# Sheet1.net
KiCad netlist of a schematic drawn in Altium Designer
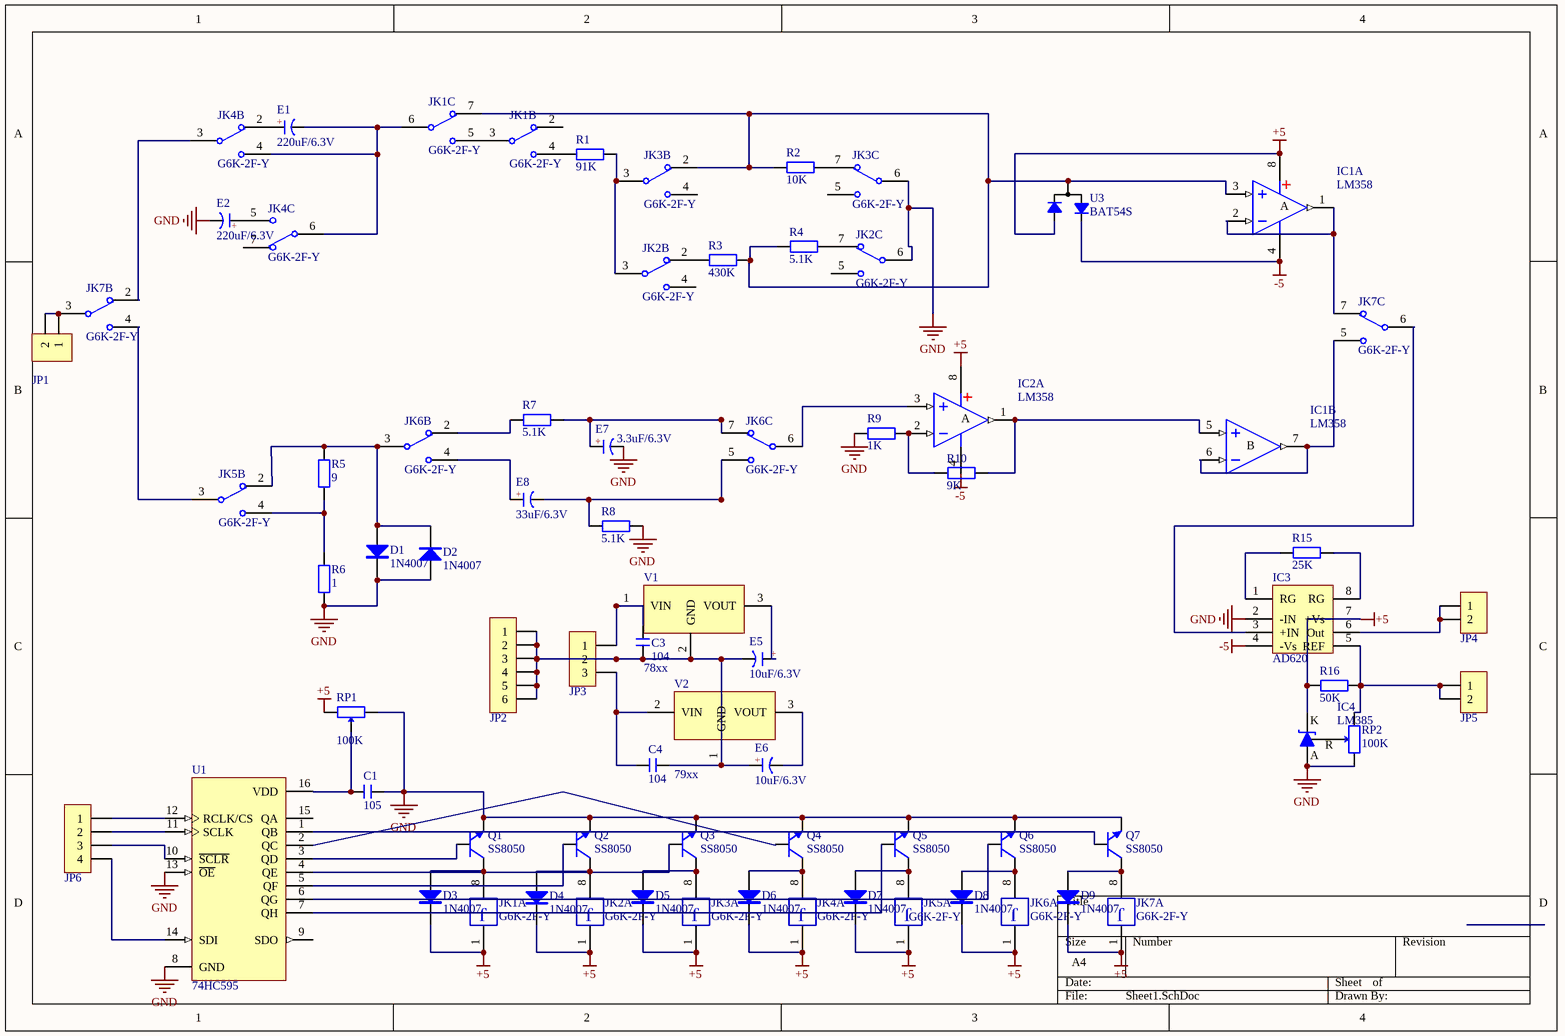
[diagram p0: Sheet1.SchDoc]

(export (version "E")
  (design (tool "Eeschema 10.0.6"))
  (components
    (comp (ref "C1")
      (value "105")
      (footprint "C 0805_L")
      (description "无极性贴片电容")
      (fields (field (name "版权归属") "源创客"))
      (libsource (lib "3.1   - 电阻-电容-电感") (part "C"))
    )
    (comp (ref "C3")
      (value "104")
      (footprint "C 0805_L")
      (description "无极性贴片电容")
      (fields (field (name "版权归属") "源创客"))
      (libsource (lib "3.1   - 电阻-电容-电感") (part "C"))
    )
    (comp (ref "C4")
      (value "104")
      (footprint "C 0805_L")
      (description "无极性贴片电容")
      (fields (field (name "版权归属") "源创客"))
      (libsource (lib "3.1   - 电阻-电容-电感") (part "C"))
    )
    (comp (ref "D1")
      (value "1N4007")
      (footprint "DO-41")
      (description "整流二极管")
      (fields (field (name "版权归属") "源创客"))
      (libsource (lib "8.1   - 二极管-整流桥") (part "1N4007"))
    )
    (comp (ref "D2")
      (value "1N4007")
      (footprint "DO-41")
      (description "整流二极管")
      (fields (field (name "版权归属") "源创客"))
      (libsource (lib "8.1   - 二极管-整流桥") (part "1N4007"))
    )
    (comp (ref "D3")
      (value "1N4007")
      (footprint "DO-41")
      (description "整流二极管")
      (fields (field (name "版权归属") "源创客"))
      (libsource (lib "8.1   - 二极管-整流桥") (part "1N4007"))
    )
    (comp (ref "D4")
      (value "1N4007")
      (footprint "DO-41")
      (description "整流二极管")
      (fields (field (name "版权归属") "源创客"))
      (libsource (lib "8.1   - 二极管-整流桥") (part "1N4007"))
    )
    (comp (ref "D5")
      (value "1N4007")
      (footprint "DO-41")
      (description "整流二极管")
      (fields (field (name "版权归属") "源创客"))
      (libsource (lib "8.1   - 二极管-整流桥") (part "1N4007"))
    )
    (comp (ref "D6")
      (value "1N4007")
      (footprint "DO-41")
      (description "整流二极管")
      (fields (field (name "版权归属") "源创客"))
      (libsource (lib "8.1   - 二极管-整流桥") (part "1N4007"))
    )
    (comp (ref "D7")
      (value "1N4007")
      (footprint "DO-41")
      (description "整流二极管")
      (fields (field (name "版权归属") "源创客"))
      (libsource (lib "8.1   - 二极管-整流桥") (part "1N4007"))
    )
    (comp (ref "D8")
      (value "1N4007")
      (footprint "DO-41")
      (description "整流二极管")
      (fields (field (name "版权归属") "源创客"))
      (libsource (lib "8.1   - 二极管-整流桥") (part "1N4007"))
    )
    (comp (ref "D9")
      (value "1N4007")
      (footprint "DO-41")
      (description "整流二极管")
      (fields (field (name "版权归属") "源创客"))
      (libsource (lib "8.1   - 二极管-整流桥") (part "1N4007"))
    )
    (comp (ref "E1")
      (value "220uF/6.3V")
      (footprint "CS 2.0*5*8 - C")
      (description "直插固态电容")
      (fields (field (name "版权归属") "源创客"))
      (libsource (lib "3.1   - 电阻-电容-电感") (part "C-CS"))
    )
    (comp (ref "E2")
      (value "220uF/6.3V")
      (footprint "CS 2.0*5*8 - C")
      (description "直插固态电容")
      (fields (field (name "版权归属") "源创客"))
      (libsource (lib "3.1   - 电阻-电容-电感") (part "C-CS"))
    )
    (comp (ref "E5")
      (value "10uF/6.3V")
      (footprint "CS 2.0*5*8 - C")
      (description "直插固态电容")
      (fields (field (name "版权归属") "源创客"))
      (libsource (lib "") (part "C-CS_1"))
    )
    (comp (ref "E6")
      (value "10uF/6.3V")
      (footprint "CS 2.0*5*8 - C")
      (description "直插固态电容")
      (fields (field (name "版权归属") "源创客"))
      (libsource (lib "3.1   - 电阻-电容-电感") (part "C-CS"))
    )
    (comp (ref "E7")
      (value "3.3uF/6.3V")
      (footprint "CS 2.0*5*8 - C")
      (description "直插固态电容")
      (fields (field (name "版权归属") "源创客"))
      (libsource (lib "3.1   - 电阻-电容-电感") (part "C-CS"))
    )
    (comp (ref "E8")
      (value "33uF/6.3V")
      (footprint "CS 2.0*5*8 - C")
      (description "直插固态电容")
      (fields (field (name "版权归属") "源创客"))
      (libsource (lib "3.1   - 电阻-电容-电感") (part "C-CS"))
    )
    (comp (ref "IC1")
      (value "LM358")
      (footprint "SOP8_N")
      (description "双路运放")
      (fields (field (name "版权归属") "源创客"))
      (libsource (lib "1.1   - IC芯片") (part "LM358"))
    )
    (comp (ref "IC2")
      (value "LM358")
      (footprint "SOP8_N")
      (description "双路运放")
      (fields (field (name "版权归属") "源创客"))
      (libsource (lib "1.1   - IC芯片") (part "LM358"))
    )
    (comp (ref "IC3")
      (value "AD620")
      (footprint "SOP8_N")
      (description "仪表放大器")
      (libsource (lib "1.1   - IC芯片") (part "AD620"))
    )
    (comp (ref "IC4")
      (value "LM385")
      (footprint "TO92A")
      (description "可调基准稳压芯片")
      (fields (field (name "版权归属") "源创客"))
      (libsource (lib "1.3   - 电源类芯片") (part "TL431-ID"))
    )
    (comp (ref "JK1")
      (value "G6K-2F-Y")
      (footprint "G6K-2F-Y")
      (description "两组转换-信号型")
      (libsource (lib "") (part "G6K-2F-Y_2"))
    )
    (comp (ref "JK2")
      (value "G6K-2F-Y")
      (footprint "G6K-2F-Y")
      (description "两组转换-信号型")
      (libsource (lib "0.9 - 继电器-变压器") (part "G6K-2F-Y"))
    )
    (comp (ref "JK3")
      (value "G6K-2F-Y")
      (footprint "G6K-2F-Y")
      (description "两组转换-信号型")
      (libsource (lib "0.9 - 继电器-变压器") (part "G6K-2F-Y"))
    )
    (comp (ref "JK4")
      (value "G6K-2F-Y")
      (footprint "G6K-2F-Y")
      (description "两组转换-信号型")
      (libsource (lib "") (part "G6K-2F-Y_1"))
    )
    (comp (ref "JK5")
      (value "G6K-2F-Y")
      (footprint "G6K-2F-Y")
      (description "两组转换-信号型")
      (libsource (lib "0.9 - 继电器-变压器") (part "G6K-2F-Y"))
    )
    (comp (ref "JK6")
      (value "G6K-2F-Y")
      (footprint "G6K-2F-Y")
      (description "两组转换-信号型")
      (libsource (lib "0.9 - 继电器-变压器") (part "G6K-2F-Y"))
    )
    (comp (ref "JK7")
      (value "G6K-2F-Y")
      (footprint "G6K-2F-Y")
      (description "两组转换-信号型")
      (libsource (lib "0.9 - 继电器-变压器") (part "G6K-2F-Y"))
    )
    (comp (ref "JP1")
      (value "HDR-1X2")
      (footprint "HDR2.54-LI-2P")
      (description "2P接插件")
      (fields (field (name "版权归属") "源创客"))
      (libsource (lib "") (part "Header 2_1"))
    )
    (comp (ref "JP2")
      (value "HDR-1X6")
      (footprint "HDR2.54-LI-6P")
      (description "6P接插件")
      (fields (field (name "版权归属") "源创客"))
      (libsource (lib "4.5   - 接插件-脚距2.54") (part "Header 6"))
    )
    (comp (ref "JP3")
      (value "HDR-1X3")
      (footprint "VH3.96-LI-3P")
      (description "3P接插件")
      (fields (field (name "版权归属") "源创客"))
      (libsource (lib "4.8   - 接插件-脚距3.96") (part "Header 3"))
    )
    (comp (ref "JP4")
      (value "HDR-1X2")
      (footprint "HDR2.54-LI-2P")
      (description "2P接插件")
      (fields (field (name "版权归属") "源创客"))
      (libsource (lib "4.5   - 接插件-脚距2.54") (part "Header 2"))
    )
    (comp (ref "JP5")
      (value "HDR-1X2")
      (footprint "HDR2.54-LI-2P")
      (description "2P接插件")
      (fields (field (name "版权归属") "源创客"))
      (libsource (lib "4.5   - 接插件-脚距2.54") (part "Header 2"))
    )
    (comp (ref "JP6")
      (value "HDR-1X4")
      (footprint "HDR2.54-LI-4P")
      (description "4P接插件")
      (fields (field (name "版权归属") "源创客"))
      (libsource (lib "4.5   - 接插件-脚距2.54") (part "Header 4"))
    )
    (comp (ref "Q1")
      (value "SS8050")
      (footprint "SOT23-3N")
      (description "高频放大-NPN型")
      (fields (field (name "版权归属") "源创客"))
      (libsource (lib "6.2   - 三极管") (part "8050-SMD"))
    )
    (comp (ref "Q2")
      (value "SS8050")
      (footprint "SOT23-3N")
      (description "高频放大-NPN型")
      (fields (field (name "版权归属") "源创客"))
      (libsource (lib "6.2   - 三极管") (part "8050-SMD"))
    )
    (comp (ref "Q3")
      (value "SS8050")
      (footprint "SOT23-3N")
      (description "高频放大-NPN型")
      (fields (field (name "版权归属") "源创客"))
      (libsource (lib "6.2   - 三极管") (part "8050-SMD"))
    )
    (comp (ref "Q4")
      (value "SS8050")
      (footprint "SOT23-3N")
      (description "高频放大-NPN型")
      (fields (field (name "版权归属") "源创客"))
      (libsource (lib "6.2   - 三极管") (part "8050-SMD"))
    )
    (comp (ref "Q5")
      (value "SS8050")
      (footprint "SOT23-3N")
      (description "高频放大-NPN型")
      (fields (field (name "版权归属") "源创客"))
      (libsource (lib "6.2   - 三极管") (part "8050-SMD"))
    )
    (comp (ref "Q6")
      (value "SS8050")
      (footprint "SOT23-3N")
      (description "高频放大-NPN型")
      (fields (field (name "版权归属") "源创客"))
      (libsource (lib "6.2   - 三极管") (part "8050-SMD"))
    )
    (comp (ref "Q7")
      (value "SS8050")
      (footprint "SOT23-3N")
      (description "高频放大-NPN型")
      (fields (field (name "版权归属") "源创客"))
      (libsource (lib "6.2   - 三极管") (part "8050-SMD"))
    )
    (comp (ref "R1")
      (value "91K")
      (footprint "R 0805_L")
      (description "贴片电阻")
      (fields (field (name "版权归属") "源创客"))
      (libsource (lib "3.1   - 电阻-电容-电感") (part "R"))
    )
    (comp (ref "R2")
      (value "10K")
      (footprint "R 0805_L")
      (description "贴片电阻")
      (fields (field (name "版权归属") "源创客"))
      (libsource (lib "3.1   - 电阻-电容-电感") (part "R"))
    )
    (comp (ref "R3")
      (value "430K")
      (footprint "R 0805_L")
      (description "贴片电阻")
      (fields (field (name "版权归属") "源创客"))
      (libsource (lib "3.1   - 电阻-电容-电感") (part "R"))
    )
    (comp (ref "R4")
      (value "5.1K")
      (footprint "R 0805_L")
      (description "贴片电阻")
      (fields (field (name "版权归属") "源创客"))
      (libsource (lib "3.1   - 电阻-电容-电感") (part "R"))
    )
    (comp (ref "R5")
      (value "9")
      (footprint "R 0805_L")
      (description "贴片电阻")
      (fields (field (name "版权归属") "源创客"))
      (libsource (lib "3.1   - 电阻-电容-电感") (part "R"))
    )
    (comp (ref "R6")
      (value "1")
      (footprint "R 0805_L")
      (description "贴片电阻")
      (fields (field (name "版权归属") "源创客"))
      (libsource (lib "3.1   - 电阻-电容-电感") (part "R"))
    )
    (comp (ref "R7")
      (value "5.1K")
      (footprint "R 0805_L")
      (description "贴片电阻")
      (fields (field (name "版权归属") "源创客"))
      (libsource (lib "3.1   - 电阻-电容-电感") (part "R"))
    )
    (comp (ref "R8")
      (value "5.1K")
      (footprint "R 0805_L")
      (description "贴片电阻")
      (fields (field (name "版权归属") "源创客"))
      (libsource (lib "3.1   - 电阻-电容-电感") (part "R"))
    )
    (comp (ref "R9")
      (value "1K")
      (footprint "R 0805_L")
      (description "贴片电阻")
      (fields (field (name "版权归属") "源创客"))
      (libsource (lib "3.1   - 电阻-电容-电感") (part "R"))
    )
    (comp (ref "R10")
      (value "9K")
      (footprint "R 0805_L")
      (description "贴片电阻")
      (fields (field (name "版权归属") "源创客"))
      (libsource (lib "3.1   - 电阻-电容-电感") (part "R"))
    )
    (comp (ref "R15")
      (value "25K")
      (footprint "R 0805_L")
      (description "贴片电阻")
      (fields (field (name "版权归属") "源创客"))
      (libsource (lib "3.1   - 电阻-电容-电感") (part "R"))
    )
    (comp (ref "R16")
      (value "50K")
      (footprint "R 0805_L")
      (description "贴片电阻")
      (fields (field (name "版权归属") "源创客"))
      (libsource (lib "3.1   - 电阻-电容-电感") (part "R"))
    )
    (comp (ref "RP1")
      (value "100K")
      (footprint "3296W")
      (description "插件单联电位器")
      (fields (field (name "版权归属") "源创客"))
      (libsource (lib "3.1   - 电阻-电容-电感") (part "RP-ID"))
    )
    (comp (ref "RP2")
      (value "100K")
      (footprint "3296W")
      (description "插件单联电位器")
      (fields (field (name "版权归属") "源创客"))
      (libsource (lib "3.1   - 电阻-电容-电感") (part "RP-ID"))
    )
    (comp (ref "U1")
      (value "74HC595")
      (footprint "SOIC-16")
      (description "移位寄存器")
      (fields (field (name "PUBLISHER") "Altium Limited"))
      (libsource (lib "CommonUsed") (part "74HC595"))
    )
    (comp (ref "U3") (value "BAT54S") (footprint "SOT-23-3") (libsource (lib "CommonUsed") (part "BAT54S")))
    (comp (ref "V1")
      (value "78xx")
      (footprint "TO220A")
      (description "线性稳压芯片")
      (fields (field (name "版权归属") "源创客"))
      (libsource (lib "1.3   - 电源类芯片") (part "78xx"))
    )
    (comp (ref "V2")
      (value "79xx")
      (footprint "TO220A")
      (description "线性稳压芯片")
      (fields (field (name "版权归属") "源创客"))
      (libsource (lib "1.3   - 电源类芯片") (part "79xx"))
    )
  )
  (nets
    (net (code "1") (name "+5") (class "Default")
      (node (ref "D3") (pin "2") (pinfunction "K_2") (pintype "passive"))
      (node (ref "D4") (pin "2") (pinfunction "K_2") (pintype "passive"))
      (node (ref "D5") (pin "2") (pinfunction "K_2") (pintype "passive"))
      (node (ref "D6") (pin "2") (pinfunction "K_2") (pintype "passive"))
      (node (ref "D7") (pin "2") (pinfunction "K_2") (pintype "passive"))
      (node (ref "D8") (pin "2") (pinfunction "K_2") (pintype "passive"))
      (node (ref "D9") (pin "2") (pinfunction "K_2") (pintype "passive"))
      (node (ref "IC1") (pin "8") (pinfunction "V+_8") (pintype "power_in"))
      (node (ref "IC2") (pin "8") (pinfunction "V+_8") (pintype "power_in"))
      (node (ref "JK1") (pin "1") (pinfunction "1_1") (pintype "passive"))
      (node (ref "JK2") (pin "1") (pinfunction "1_1") (pintype "passive"))
      (node (ref "JK3") (pin "1") (pinfunction "1_1") (pintype "passive"))
      (node (ref "JK4") (pin "1") (pinfunction "1_1") (pintype "passive"))
      (node (ref "JK5") (pin "1") (pinfunction "1_1") (pintype "passive"))
      (node (ref "JK6") (pin "1") (pinfunction "1_1") (pintype "passive"))
      (node (ref "JK7") (pin "1") (pinfunction "1_1") (pintype "passive"))
      (node (ref "RP1") (pin "3") (pinfunction "3_3") (pintype "passive"))
      (node (ref "U3") (pin "1") (pinfunction "1_1") (pintype "passive"))
    )
    (net (code "2") (name "-5") (class "Default")
      (node (ref "IC1") (pin "4") (pinfunction "V-_4") (pintype "power_in"))
      (node (ref "IC2") (pin "4") (pinfunction "V-_4") (pintype "power_in"))
      (node (ref "IC3") (pin "4") (pinfunction "-Vs_4") (pintype "passive"))
      (node (ref "U3") (pin "3") (pinfunction "3_3") (pintype "passive"))
    )
    (net (code "3") (name "GND") (class "Default")
      (node (ref "C1") (pin "2") (pinfunction "2_2") (pintype "passive"))
      (node (ref "D1") (pin "2") (pinfunction "K_2") (pintype "passive"))
      (node (ref "D2") (pin "1") (pinfunction "A_1") (pintype "passive"))
      (node (ref "E2") (pin "2") (pinfunction "K_2") (pintype "passive"))
      (node (ref "E7") (pin "2") (pinfunction "K_2") (pintype "passive"))
      (node (ref "IC3") (pin "2") (pinfunction "-IN_2") (pintype "passive"))
      (node (ref "IC4") (pin "2") (pinfunction "A_2") (pintype "passive"))
      (node (ref "JK2") (pin "6") (pinfunction "6_6") (pintype "passive"))
      (node (ref "JK3") (pin "6") (pinfunction "6_6") (pintype "passive"))
      (node (ref "Q1") (pin "2") (pinfunction "E_2") (pintype "passive"))
      (node (ref "Q2") (pin "2") (pinfunction "E_2") (pintype "passive"))
      (node (ref "Q3") (pin "2") (pinfunction "E_2") (pintype "passive"))
      (node (ref "Q4") (pin "2") (pinfunction "E_2") (pintype "passive"))
      (node (ref "Q5") (pin "2") (pinfunction "E_2") (pintype "passive"))
      (node (ref "Q6") (pin "2") (pinfunction "E_2") (pintype "passive"))
      (node (ref "Q7") (pin "2") (pinfunction "E_2") (pintype "passive"))
      (node (ref "R6") (pin "1") (pinfunction "1_1") (pintype "passive"))
      (node (ref "R8") (pin "2") (pinfunction "2_2") (pintype "passive"))
      (node (ref "R9") (pin "1") (pinfunction "1_1") (pintype "passive"))
      (node (ref "RP1") (pin "1") (pinfunction "1_1") (pintype "passive"))
      (node (ref "RP2") (pin "3") (pinfunction "3_3") (pintype "passive"))
      (node (ref "U1") (pin "13") (pinfunction "~{OE}_13") (pintype "input"))
      (node (ref "U1") (pin "8") (pinfunction "GND_8") (pintype "power_in"))
    )
    (net (code "4") (name "Net-(D1-A)") (class "Default")
      (node (ref "D1") (pin "1") (pinfunction "A_1") (pintype "passive"))
      (node (ref "D2") (pin "2") (pinfunction "K_2") (pintype "passive"))
      (node (ref "JK5") (pin "2") (pinfunction "2_2") (pintype "passive"))
      (node (ref "JK6") (pin "3") (pinfunction "3_3") (pintype "passive"))
      (node (ref "R5") (pin "1") (pinfunction "1_1") (pintype "passive"))
    )
    (net (code "5") (name "Net-(D3-A)") (class "Default")
      (node (ref "D3") (pin "1") (pinfunction "A_1") (pintype "passive"))
      (node (ref "JK1") (pin "8") (pinfunction "8_8") (pintype "passive"))
      (node (ref "Q1") (pin "3") (pinfunction "C_3") (pintype "passive"))
    )
    (net (code "6") (name "Net-(D4-A)") (class "Default")
      (node (ref "D4") (pin "1") (pinfunction "A_1") (pintype "passive"))
      (node (ref "JK2") (pin "8") (pinfunction "8_8") (pintype "passive"))
      (node (ref "Q2") (pin "3") (pinfunction "C_3") (pintype "passive"))
    )
    (net (code "7") (name "Net-(D5-A)") (class "Default")
      (node (ref "D5") (pin "1") (pinfunction "A_1") (pintype "passive"))
      (node (ref "JK3") (pin "8") (pinfunction "8_8") (pintype "passive"))
      (node (ref "Q3") (pin "3") (pinfunction "C_3") (pintype "passive"))
    )
    (net (code "8") (name "Net-(D6-A)") (class "Default")
      (node (ref "D6") (pin "1") (pinfunction "A_1") (pintype "passive"))
      (node (ref "JK4") (pin "8") (pinfunction "8_8") (pintype "passive"))
      (node (ref "Q4") (pin "3") (pinfunction "C_3") (pintype "passive"))
    )
    (net (code "9") (name "Net-(D7-A)") (class "Default")
      (node (ref "D7") (pin "1") (pinfunction "A_1") (pintype "passive"))
      (node (ref "JK5") (pin "8") (pinfunction "8_8") (pintype "passive"))
      (node (ref "Q5") (pin "3") (pinfunction "C_3") (pintype "passive"))
    )
    (net (code "10") (name "Net-(D8-A)") (class "Default")
      (node (ref "D8") (pin "1") (pinfunction "A_1") (pintype "passive"))
      (node (ref "JK6") (pin "8") (pinfunction "8_8") (pintype "passive"))
      (node (ref "Q6") (pin "3") (pinfunction "C_3") (pintype "passive"))
    )
    (net (code "11") (name "Net-(D9-A)") (class "Default")
      (node (ref "D9") (pin "1") (pinfunction "A_1") (pintype "passive"))
      (node (ref "JK7") (pin "8") (pinfunction "8_8") (pintype "passive"))
      (node (ref "Q7") (pin "3") (pinfunction "C_3") (pintype "passive"))
    )
    (net (code "12") (name "Net-(E1-A)") (class "Default")
      (node (ref "E1") (pin "1") (pinfunction "A_1") (pintype "passive"))
      (node (ref "JK4") (pin "2") (pinfunction "2_2") (pintype "passive"))
    )
    (net (code "13") (name "Net-(E1-K)") (class "Default")
      (node (ref "E1") (pin "2") (pinfunction "K_2") (pintype "passive"))
      (node (ref "JK1") (pin "6") (pinfunction "6_6") (pintype "passive"))
      (node (ref "JK4") (pin "4") (pinfunction "4_4") (pintype "passive"))
      (node (ref "JK4") (pin "6") (pinfunction "6_6") (pintype "passive"))
    )
    (net (code "14") (name "Net-(E2-A)") (class "Default")
      (node (ref "E2") (pin "1") (pinfunction "A_1") (pintype "passive"))
      (node (ref "JK4") (pin "5") (pinfunction "5_5") (pintype "passive"))
    )
    (net (code "15") (name "Net-(E5-A)") (class "Default")
      (node (ref "E5") (pin "1") (pinfunction "A_1") (pintype "passive"))
      (node (ref "V1") (pin "3") (pinfunction "VOUT_3") (pintype "passive"))
    )
    (net (code "16") (name "Net-(E5-K)") (class "Default")
      (node (ref "C3") (pin "1") (pinfunction "1_1") (pintype "passive"))
      (node (ref "C4") (pin "2") (pinfunction "2_2") (pintype "passive"))
      (node (ref "E5") (pin "2") (pinfunction "K_2") (pintype "passive"))
      (node (ref "E6") (pin "1") (pinfunction "A_1") (pintype "passive"))
      (node (ref "JP2") (pin "1") (pinfunction "1_1") (pintype "passive"))
      (node (ref "JP2") (pin "2") (pinfunction "2_2") (pintype "passive"))
      (node (ref "JP2") (pin "3") (pinfunction "3_3") (pintype "passive"))
      (node (ref "JP2") (pin "4") (pinfunction "4_4") (pintype "passive"))
      (node (ref "JP2") (pin "5") (pinfunction "5_5") (pintype "passive"))
      (node (ref "JP2") (pin "6") (pinfunction "6_6") (pintype "passive"))
      (node (ref "JP3") (pin "2") (pinfunction "2_2") (pintype "passive"))
      (node (ref "V1") (pin "2") (pinfunction "GND_2") (pintype "passive"))
      (node (ref "V2") (pin "1") (pinfunction "GND_1") (pintype "passive"))
    )
    (net (code "17") (name "Net-(E6-K)") (class "Default")
      (node (ref "E6") (pin "2") (pinfunction "K_2") (pintype "passive"))
      (node (ref "V2") (pin "3") (pinfunction "VOUT_3") (pintype "passive"))
    )
    (net (code "18") (name "Net-(E7-A)") (class "Default")
      (node (ref "E7") (pin "1") (pinfunction "A_1") (pintype "passive"))
      (node (ref "JK6") (pin "7") (pinfunction "7_7") (pintype "passive"))
      (node (ref "R7") (pin "2") (pinfunction "2_2") (pintype "passive"))
    )
    (net (code "19") (name "Net-(E8-A)") (class "Default")
      (node (ref "E8") (pin "1") (pinfunction "A_1") (pintype "passive"))
      (node (ref "JK6") (pin "4") (pinfunction "4_4") (pintype "passive"))
    )
    (net (code "20") (name "Net-(E8-K)") (class "Default")
      (node (ref "E8") (pin "2") (pinfunction "K_2") (pintype "passive"))
      (node (ref "JK6") (pin "5") (pinfunction "5_5") (pintype "passive"))
      (node (ref "R8") (pin "1") (pinfunction "1_1") (pintype "passive"))
    )
    (net (code "21") (name "Net-(IC1A-IN+)") (class "Default")
      (node (ref "IC1") (pin "3") (pinfunction "IN+_3") (pintype "input"))
      (node (ref "JK1") (pin "7") (pinfunction "7_7") (pintype "passive"))
      (node (ref "JK3") (pin "2") (pinfunction "2_2") (pintype "passive"))
      (node (ref "R2") (pin "1") (pinfunction "1_1") (pintype "passive"))
      (node (ref "R3") (pin "2") (pinfunction "2_2") (pintype "passive"))
      (node (ref "R4") (pin "1") (pinfunction "1_1") (pintype "passive"))
      (node (ref "U3") (pin "2") (pinfunction "2_2") (pintype "passive"))
    )
    (net (code "22") (name "Net-(IC1A-IN-)") (class "Default")
      (node (ref "IC1") (pin "1") (pinfunction "OUT_1") (pintype "output"))
      (node (ref "IC1") (pin "2") (pinfunction "IN-_2") (pintype "input"))
      (node (ref "JK7") (pin "7") (pinfunction "7_7") (pintype "passive"))
    )
    (net (code "23") (name "Net-(IC1B-IN+)") (class "Default")
      (node (ref "IC1") (pin "5") (pinfunction "IN+_5") (pintype "input"))
      (node (ref "IC2") (pin "1") (pinfunction "OUT_1") (pintype "output"))
      (node (ref "R10") (pin "2") (pinfunction "2_2") (pintype "passive"))
    )
    (net (code "24") (name "Net-(IC1B-IN-)") (class "Default")
      (node (ref "IC1") (pin "6") (pinfunction "IN-_6") (pintype "input"))
      (node (ref "IC1") (pin "7") (pinfunction "OUT_7") (pintype "output"))
      (node (ref "JK7") (pin "5") (pinfunction "5_5") (pintype "passive"))
    )
    (net (code "25") (name "Net-(IC2A-IN+)") (class "Default")
      (node (ref "IC2") (pin "3") (pinfunction "IN+_3") (pintype "input"))
      (node (ref "JK6") (pin "6") (pinfunction "6_6") (pintype "passive"))
    )
    (net (code "26") (name "Net-(IC2A-IN-)") (class "Default")
      (node (ref "IC2") (pin "2") (pinfunction "IN-_2") (pintype "input"))
      (node (ref "R10") (pin "1") (pinfunction "1_1") (pintype "passive"))
      (node (ref "R9") (pin "2") (pinfunction "2_2") (pintype "passive"))
    )
    (net (code "27") (name "Net-(IC3-+IN)") (class "Default")
      (node (ref "IC3") (pin "3") (pinfunction "+IN_3") (pintype "passive"))
      (node (ref "JK7") (pin "6") (pinfunction "6_6") (pintype "passive"))
    )
    (net (code "28") (name "Net-(IC3-+Vs)") (class "Default")
      (node (ref "IC3") (pin "7") (pinfunction "+Vs_7") (pintype "passive"))
      (node (ref "IC4") (pin "3") (pinfunction "K_3") (pintype "passive"))
      (node (ref "R16") (pin "1") (pinfunction "1_1") (pintype "passive"))
    )
    (net (code "29") (name "Net-(IC3-Out)") (class "Default")
      (node (ref "IC3") (pin "6") (pinfunction "Out_6") (pintype "passive"))
      (node (ref "JP4") (pin "1") (pinfunction "1_1") (pintype "passive"))
      (node (ref "JP4") (pin "2") (pinfunction "2_2") (pintype "passive"))
    )
    (net (code "30") (name "Net-(IC3-REF)") (class "Default")
      (node (ref "IC3") (pin "5") (pinfunction "REF_5") (pintype "passive"))
      (node (ref "JP5") (pin "1") (pinfunction "1_1") (pintype "passive"))
      (node (ref "JP5") (pin "2") (pinfunction "2_2") (pintype "passive"))
      (node (ref "R16") (pin "2") (pinfunction "2_2") (pintype "passive"))
      (node (ref "RP2") (pin "1") (pinfunction "1_1") (pintype "passive"))
    )
    (net (code "31") (name "Net-(IC3-RG-Pad1)") (class "Default")
      (node (ref "IC3") (pin "1") (pinfunction "RG_1") (pintype "passive"))
      (node (ref "R15") (pin "1") (pinfunction "1_1") (pintype "passive"))
    )
    (net (code "32") (name "Net-(IC3-RG-Pad8)") (class "Default")
      (node (ref "IC3") (pin "8") (pinfunction "RG_8") (pintype "passive"))
      (node (ref "R15") (pin "2") (pinfunction "2_2") (pintype "passive"))
    )
    (net (code "33") (name "Net-(IC4-R)") (class "Default")
      (node (ref "IC4") (pin "1") (pinfunction "R_1") (pintype "passive"))
      (node (ref "RP2") (pin "2") (pinfunction "2_2") (pintype "passive"))
    )
    (net (code "34") (name "Net-(JK1-Pad3)") (class "Default")
      (node (ref "JK1") (pin "3") (pinfunction "3_3") (pintype "passive"))
      (node (ref "JK1") (pin "5") (pinfunction "5_5") (pintype "passive"))
    )
    (net (code "35") (name "Net-(JK1-Pad4)") (class "Default")
      (node (ref "JK1") (pin "4") (pinfunction "4_4") (pintype "passive"))
      (node (ref "R1") (pin "1") (pinfunction "1_1") (pintype "passive"))
    )
    (net (code "36") (name "Net-(JK2-Pad2)") (class "Default")
      (node (ref "JK2") (pin "2") (pinfunction "2_2") (pintype "passive"))
      (node (ref "R3") (pin "1") (pinfunction "1_1") (pintype "passive"))
    )
    (net (code "37") (name "Net-(JK2-Pad3)") (class "Default")
      (node (ref "JK2") (pin "3") (pinfunction "3_3") (pintype "passive"))
      (node (ref "JK3") (pin "3") (pinfunction "3_3") (pintype "passive"))
      (node (ref "R1") (pin "2") (pinfunction "2_2") (pintype "passive"))
    )
    (net (code "38") (name "Net-(JK2-Pad7)") (class "Default")
      (node (ref "JK2") (pin "7") (pinfunction "7_7") (pintype "passive"))
      (node (ref "R4") (pin "2") (pinfunction "2_2") (pintype "passive"))
    )
    (net (code "39") (name "Net-(JK3-Pad7)") (class "Default")
      (node (ref "JK3") (pin "7") (pinfunction "7_7") (pintype "passive"))
      (node (ref "R2") (pin "2") (pinfunction "2_2") (pintype "passive"))
    )
    (net (code "40") (name "Net-(JK4-Pad3)") (class "Default")
      (node (ref "JK4") (pin "3") (pinfunction "3_3") (pintype "passive"))
      (node (ref "JK7") (pin "2") (pinfunction "2_2") (pintype "passive"))
    )
    (net (code "41") (name "Net-(JK5-Pad3)") (class "Default")
      (node (ref "JK5") (pin "3") (pinfunction "3_3") (pintype "passive"))
      (node (ref "JK7") (pin "4") (pinfunction "4_4") (pintype "passive"))
    )
    (net (code "42") (name "Net-(JK5-Pad4)") (class "Default")
      (node (ref "JK5") (pin "4") (pinfunction "4_4") (pintype "passive"))
      (node (ref "R5") (pin "2") (pinfunction "2_2") (pintype "passive"))
      (node (ref "R6") (pin "2") (pinfunction "2_2") (pintype "passive"))
    )
    (net (code "43") (name "Net-(JK6-Pad2)") (class "Default")
      (node (ref "JK6") (pin "2") (pinfunction "2_2") (pintype "passive"))
      (node (ref "R7") (pin "1") (pinfunction "1_1") (pintype "passive"))
    )
    (net (code "44") (name "Net-(JK7-Pad3)") (class "Default")
      (node (ref "JK7") (pin "3") (pinfunction "3_3") (pintype "passive"))
      (node (ref "JP1") (pin "1") (pinfunction "1_1") (pintype "passive"))
      (node (ref "JP1") (pin "2") (pinfunction "2_2") (pintype "passive"))
    )
    (net (code "45") (name "Net-(Q1-B)") (class "Default")
      (node (ref "Q1") (pin "1") (pinfunction "B_1") (pintype "passive"))
      (node (ref "U1") (pin "3") (pinfunction "QD_3") (pintype "tri_state"))
    )
    (net (code "46") (name "Net-(Q2-B)") (class "Default")
      (node (ref "Q2") (pin "1") (pinfunction "B_1") (pintype "passive"))
      (node (ref "U1") (pin "5") (pinfunction "QF_5") (pintype "tri_state"))
    )
    (net (code "47") (name "Net-(Q3-B)") (class "Default")
      (node (ref "Q3") (pin "1") (pinfunction "B_1") (pintype "passive"))
      (node (ref "U1") (pin "4") (pinfunction "QE_4") (pintype "tri_state"))
    )
    (net (code "48") (name "Net-(Q4-B)") (class "Default")
      (node (ref "Q4") (pin "1") (pinfunction "B_1") (pintype "passive"))
      (node (ref "U1") (pin "2") (pinfunction "QC_2") (pintype "tri_state"))
    )
    (net (code "49") (name "Net-(Q5-B)") (class "Default")
      (node (ref "Q5") (pin "1") (pinfunction "B_1") (pintype "passive"))
      (node (ref "U1") (pin "7") (pinfunction "QH_7") (pintype "tri_state"))
    )
    (net (code "50") (name "Net-(Q6-B)") (class "Default")
      (node (ref "Q6") (pin "1") (pinfunction "B_1") (pintype "passive"))
      (node (ref "U1") (pin "6") (pinfunction "QG_6") (pintype "tri_state"))
    )
    (net (code "51") (name "Net-(Q7-B)") (class "Default")
      (node (ref "Q7") (pin "1") (pinfunction "B_1") (pintype "passive"))
      (node (ref "U1") (pin "1") (pinfunction "QB_1") (pintype "tri_state"))
    )
    (net (code "52") (name "Net-(U1-RCLK{slash}CS)") (class "Default")
      (node (ref "JP6") (pin "1") (pinfunction "1_1") (pintype "passive"))
      (node (ref "U1") (pin "12") (pinfunction "RCLK/CS_12") (pintype "input"))
    )
    (net (code "53") (name "Net-(U1-SCLK)") (class "Default")
      (node (ref "JP6") (pin "2") (pinfunction "2_2") (pintype "passive"))
      (node (ref "U1") (pin "11") (pinfunction "SCLK_11") (pintype "input"))
    )
    (net (code "54") (name "Net-(U1-SDI)") (class "Default")
      (node (ref "JP6") (pin "4") (pinfunction "4_4") (pintype "passive"))
      (node (ref "U1") (pin "14") (pinfunction "SDI_14") (pintype "input"))
    )
    (net (code "55") (name "Net-(U1-VDD)") (class "Default")
      (node (ref "C1") (pin "1") (pinfunction "1_1") (pintype "passive"))
      (node (ref "RP1") (pin "2") (pinfunction "2_2") (pintype "passive"))
      (node (ref "U1") (pin "16") (pinfunction "VDD_16") (pintype "power_in"))
    )
    (net (code "56") (name "Net-(U1-~{SCLR})") (class "Default")
      (node (ref "JP6") (pin "3") (pinfunction "3_3") (pintype "passive"))
      (node (ref "U1") (pin "10") (pinfunction "~{SCLR}_10") (pintype "input"))
    )
    (net (code "57") (name "Net-(V1-VIN)") (class "Default")
      (node (ref "C3") (pin "2") (pinfunction "2_2") (pintype "passive"))
      (node (ref "JP3") (pin "1") (pinfunction "1_1") (pintype "passive"))
      (node (ref "V1") (pin "1") (pinfunction "VIN_1") (pintype "passive"))
    )
    (net (code "58") (name "Net-(V2-VIN)") (class "Default")
      (node (ref "C4") (pin "1") (pinfunction "1_1") (pintype "passive"))
      (node (ref "JP3") (pin "3") (pinfunction "3_3") (pintype "passive"))
      (node (ref "V2") (pin "2") (pinfunction "VIN_2") (pintype "passive"))
    )
    (net (code "59") (name "unconnected-(JK1-Pad2)") (class "Default")
      (node (ref "JK1") (pin "2") (pinfunction "2_2") (pintype "passive"))
    )
    (net (code "60") (name "unconnected-(JK2-Pad4)") (class "Default")
      (node (ref "JK2") (pin "4") (pinfunction "4_4") (pintype "passive"))
    )
    (net (code "61") (name "unconnected-(JK2-Pad5)") (class "Default")
      (node (ref "JK2") (pin "5") (pinfunction "5_5") (pintype "passive"))
    )
    (net (code "62") (name "unconnected-(JK3-Pad4)") (class "Default")
      (node (ref "JK3") (pin "4") (pinfunction "4_4") (pintype "passive"))
    )
    (net (code "63") (name "unconnected-(JK3-Pad5)") (class "Default")
      (node (ref "JK3") (pin "5") (pinfunction "5_5") (pintype "passive"))
    )
    (net (code "64") (name "unconnected-(JK4-Pad7)") (class "Default")
      (node (ref "JK4") (pin "7") (pinfunction "7_7") (pintype "passive"))
    )
    (net (code "65") (name "unconnected-(U1-QA-Pad15)") (class "Default")
      (node (ref "U1") (pin "15") (pinfunction "QA_15") (pintype "tri_state"))
    )
    (net (code "66") (name "unconnected-(U1-SDO-Pad9)") (class "Default")
      (node (ref "U1") (pin "9") (pinfunction "SDO_9") (pintype "output"))
    )
  )
)
